# main.net
KiCad netlist of a schematic drawn in Altium Designer
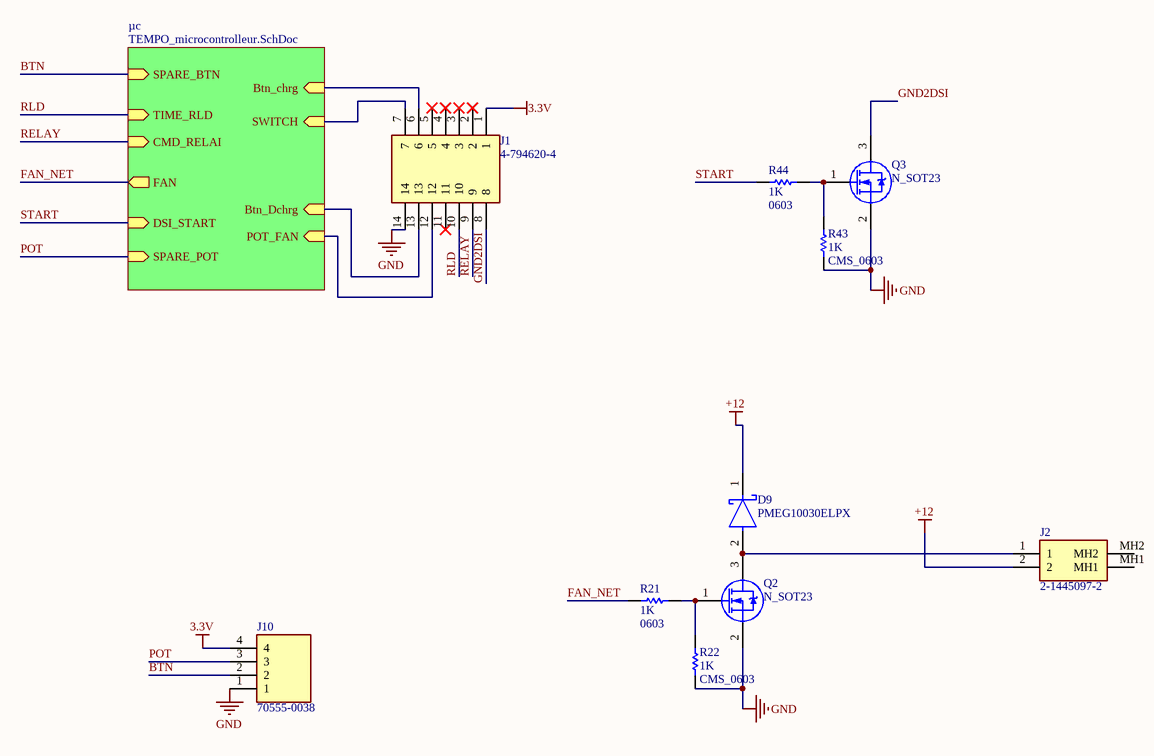
[diagram p0: main.SchDoc]

(export (version "E")
  (design (tool "Eeschema 10.0.6"))
  (components
    (comp (ref "D9")
      (value "PMEG10030ELPX")
      (footprint "FP-SOD128-MFG")
      (description "DIODE SCHOTTKY 100V 3A SOD128")
      (libsource (lib "Altium Content Vault") (part "fefb30dabb5d097ae2f038500735429"))
    )
    (comp (ref "J1")
      (value "4-794620-4")
      (footprint "214450973:4-794620-4")
      (description "Connector")
      (fields (field (name "MOUSER PART NUMBER") "571-4-794620-4"))
      (libsource (lib "*") (part "4-794620-4"))
    )
    (comp (ref "J2")
      (value "2-1445097-2")
      (footprint "214450972")
      (description "MICRO MNL HDR ASSY S/ROW AU LF")
      (fields (field (name "MOUSER PART NUMBER") "571-2-1445097-2"))
      (libsource (lib "2-1445097-2") (part "2-1445097-2"))
    )
    (comp (ref "J10")
      (value "70555-0038")
      (footprint "214450973:705550038")
      (description "Connector")
      (fields (field (name "RS PART NUMBER") "7978792P"))
      (libsource (lib "2-1445097-3") (part "70555-0038"))
    )
    (comp (ref "Q2")
      (value "TRANSISTOR_MOSFET-N_SOT23_GSD")
      (footprint "TRANSISTOR_MOSFET-N_SOT23_GSD")
      (description "TRANSISTOR MOSFET CANAL N BOITIER SOT23_GSD")
      (fields (field (name "PACKAGE") "N_SOT23"))
      (libsource (lib "composants actifs") (part "TRANSISTOR_MOSFET-N_SOT23_GSD"))
    )
    (comp (ref "Q3")
      (value "TRANSISTOR_MOSFET-N_SOT23_GSD")
      (footprint "TRANSISTOR_MOSFET-N_SOT23_GSD")
      (description "TRANSISTOR MOSFET CANAL N BOITIER SOT23_GSD")
      (fields (field (name "PACKAGE") "N_SOT23"))
      (libsource (lib "composants actifs") (part "TRANSISTOR_MOSFET-N_SOT23_GSD"))
    )
    (comp (ref "R21")
      (value "1K")
      (footprint "RESISTANCE_CMS_0603")
      (description "RESISTANCE CMS 0603")
      (fields (field (name "TYPE") "0603") (field (name "Comment") "RESISTANCE_CMS_0603"))
      (libsource (lib "composants passifs") (part "RESISTANCE_CMS_0603"))
    )
    (comp (ref "R22")
      (value "1K")
      (footprint "RESISTANCE_CMS_0603")
      (description "RESISTANCE CMS 0603")
      (fields (field (name "TYPE") "CMS_0603") (field (name "Comment") "RESISTANCE_CMS_0603"))
      (libsource (lib "composants passifs") (part "RESISTANCE_CMS_0603"))
    )
    (comp (ref "R43")
      (value "1K")
      (footprint "RESISTANCE_CMS_0603")
      (description "RESISTANCE CMS 0603")
      (fields (field (name "TYPE") "CMS_0603") (field (name "Comment") "RESISTANCE_CMS_0603"))
      (libsource (lib "composants passifs") (part "RESISTANCE_CMS_0603"))
    )
    (comp (ref "R44")
      (value "1K")
      (footprint "RESISTANCE_CMS_0603")
      (description "RESISTANCE CMS 0603")
      (fields (field (name "TYPE") "0603") (field (name "Comment") "RESISTANCE_CMS_0603"))
      (libsource (lib "composants passifs") (part "RESISTANCE_CMS_0603"))
    )
  )
  (nets
    (net (code "1") (name "+12") (class "Default")
      (node (ref "D9") (pin "1") (pinfunction "K_1") (pintype "passive"))
      (node (ref "J2") (pin "2") (pinfunction "2_2") (pintype "passive"))
    )
    (net (code "2") (name "/BTN") (class "Default")
      (node (ref "J10") (pin "2") (pinfunction "2_2") (pintype "passive"))
    )
    (net (code "3") (name "/Btn_Dchrg") (class "Default")
      (node (ref "J1") (pin "13") (pinfunction "13_13") (pintype "passive"))
    )
    (net (code "4") (name "/Btn_chrg") (class "Default")
      (node (ref "J1") (pin "6") (pinfunction "6_6") (pintype "passive"))
    )
    (net (code "5") (name "/FAN_NET") (class "Default")
      (node (ref "R21") (pin "2") (pinfunction "2_2") (pintype "passive"))
    )
    (net (code "6") (name "/GND2DSI") (class "Default")
      (node (ref "J1") (pin "8") (pinfunction "8_8") (pintype "passive"))
      (node (ref "Q3") (pin "3") (pinfunction "D_3") (pintype "passive"))
    )
    (net (code "7") (name "/POT") (class "Default")
      (node (ref "J10") (pin "3") (pinfunction "3_3") (pintype "passive"))
    )
    (net (code "8") (name "/POT_FAN") (class "Default")
      (node (ref "J1") (pin "12") (pinfunction "12_12") (pintype "passive"))
    )
    (net (code "9") (name "/RELAY") (class "Default")
      (node (ref "J1") (pin "9") (pinfunction "9_9") (pintype "passive"))
    )
    (net (code "10") (name "/RLD") (class "Default")
      (node (ref "J1") (pin "10") (pinfunction "10_10") (pintype "passive"))
    )
    (net (code "11") (name "/START") (class "Default")
      (node (ref "R44") (pin "2") (pinfunction "2_2") (pintype "passive"))
    )
    (net (code "12") (name "/SWITCH") (class "Default")
      (node (ref "J1") (pin "7") (pinfunction "7_7") (pintype "passive"))
    )
    (net (code "13") (name "3.3V") (class "Default")
      (node (ref "J1") (pin "1") (pinfunction "1_1") (pintype "passive"))
      (node (ref "J10") (pin "4") (pinfunction "4_4") (pintype "passive"))
    )
    (net (code "14") (name "GND") (class "Default")
      (node (ref "J1") (pin "14") (pinfunction "14_14") (pintype "passive"))
      (node (ref "J10") (pin "1") (pinfunction "1_1") (pintype "passive"))
      (node (ref "Q2") (pin "2") (pinfunction "S_2") (pintype "passive"))
      (node (ref "Q3") (pin "2") (pinfunction "S_2") (pintype "passive"))
      (node (ref "R22") (pin "2") (pinfunction "2_2") (pintype "passive"))
      (node (ref "R43") (pin "2") (pinfunction "2_2") (pintype "passive"))
    )
    (net (code "15") (name "Net-(D9-A)") (class "Default")
      (node (ref "D9") (pin "2") (pinfunction "A_2") (pintype "passive"))
      (node (ref "J2") (pin "1") (pinfunction "1_1") (pintype "passive"))
      (node (ref "Q2") (pin "3") (pinfunction "D_3") (pintype "passive"))
    )
    (net (code "16") (name "Net-(Q2-G)") (class "Default")
      (node (ref "Q2") (pin "1") (pinfunction "G_1") (pintype "passive"))
      (node (ref "R21") (pin "1") (pinfunction "1_1") (pintype "passive"))
      (node (ref "R22") (pin "1") (pinfunction "1_1") (pintype "passive"))
    )
    (net (code "17") (name "Net-(Q3-G)") (class "Default")
      (node (ref "Q3") (pin "1") (pinfunction "G_1") (pintype "passive"))
      (node (ref "R43") (pin "1") (pinfunction "1_1") (pintype "passive"))
      (node (ref "R44") (pin "1") (pinfunction "1_1") (pintype "passive"))
    )
    (net (code "18") (name "unconnected-(J1-Pad2)") (class "Default")
      (node (ref "J1") (pin "2") (pinfunction "2_2") (pintype "passive+no_connect"))
    )
    (net (code "19") (name "unconnected-(J1-Pad3)") (class "Default")
      (node (ref "J1") (pin "3") (pinfunction "3_3") (pintype "passive+no_connect"))
    )
    (net (code "20") (name "unconnected-(J1-Pad4)") (class "Default")
      (node (ref "J1") (pin "4") (pinfunction "4_4") (pintype "passive+no_connect"))
    )
    (net (code "21") (name "unconnected-(J1-Pad5)") (class "Default")
      (node (ref "J1") (pin "5") (pinfunction "5_5") (pintype "passive+no_connect"))
    )
    (net (code "22") (name "unconnected-(J1-Pad11)") (class "Default")
      (node (ref "J1") (pin "11") (pinfunction "11_11") (pintype "passive+no_connect"))
    )
    (net (code "23") (name "unconnected-(J2-PadMH1)") (class "Default")
      (node (ref "J2") (pin "MH1") (pinfunction "MH1_MH1") (pintype "passive"))
    )
    (net (code "24") (name "unconnected-(J2-PadMH2)") (class "Default")
      (node (ref "J2") (pin "MH2") (pinfunction "MH2_MH2") (pintype "passive"))
    )
  )
)
